# prototype.net
KiCad netlist of a schematic drawn in EAGLE
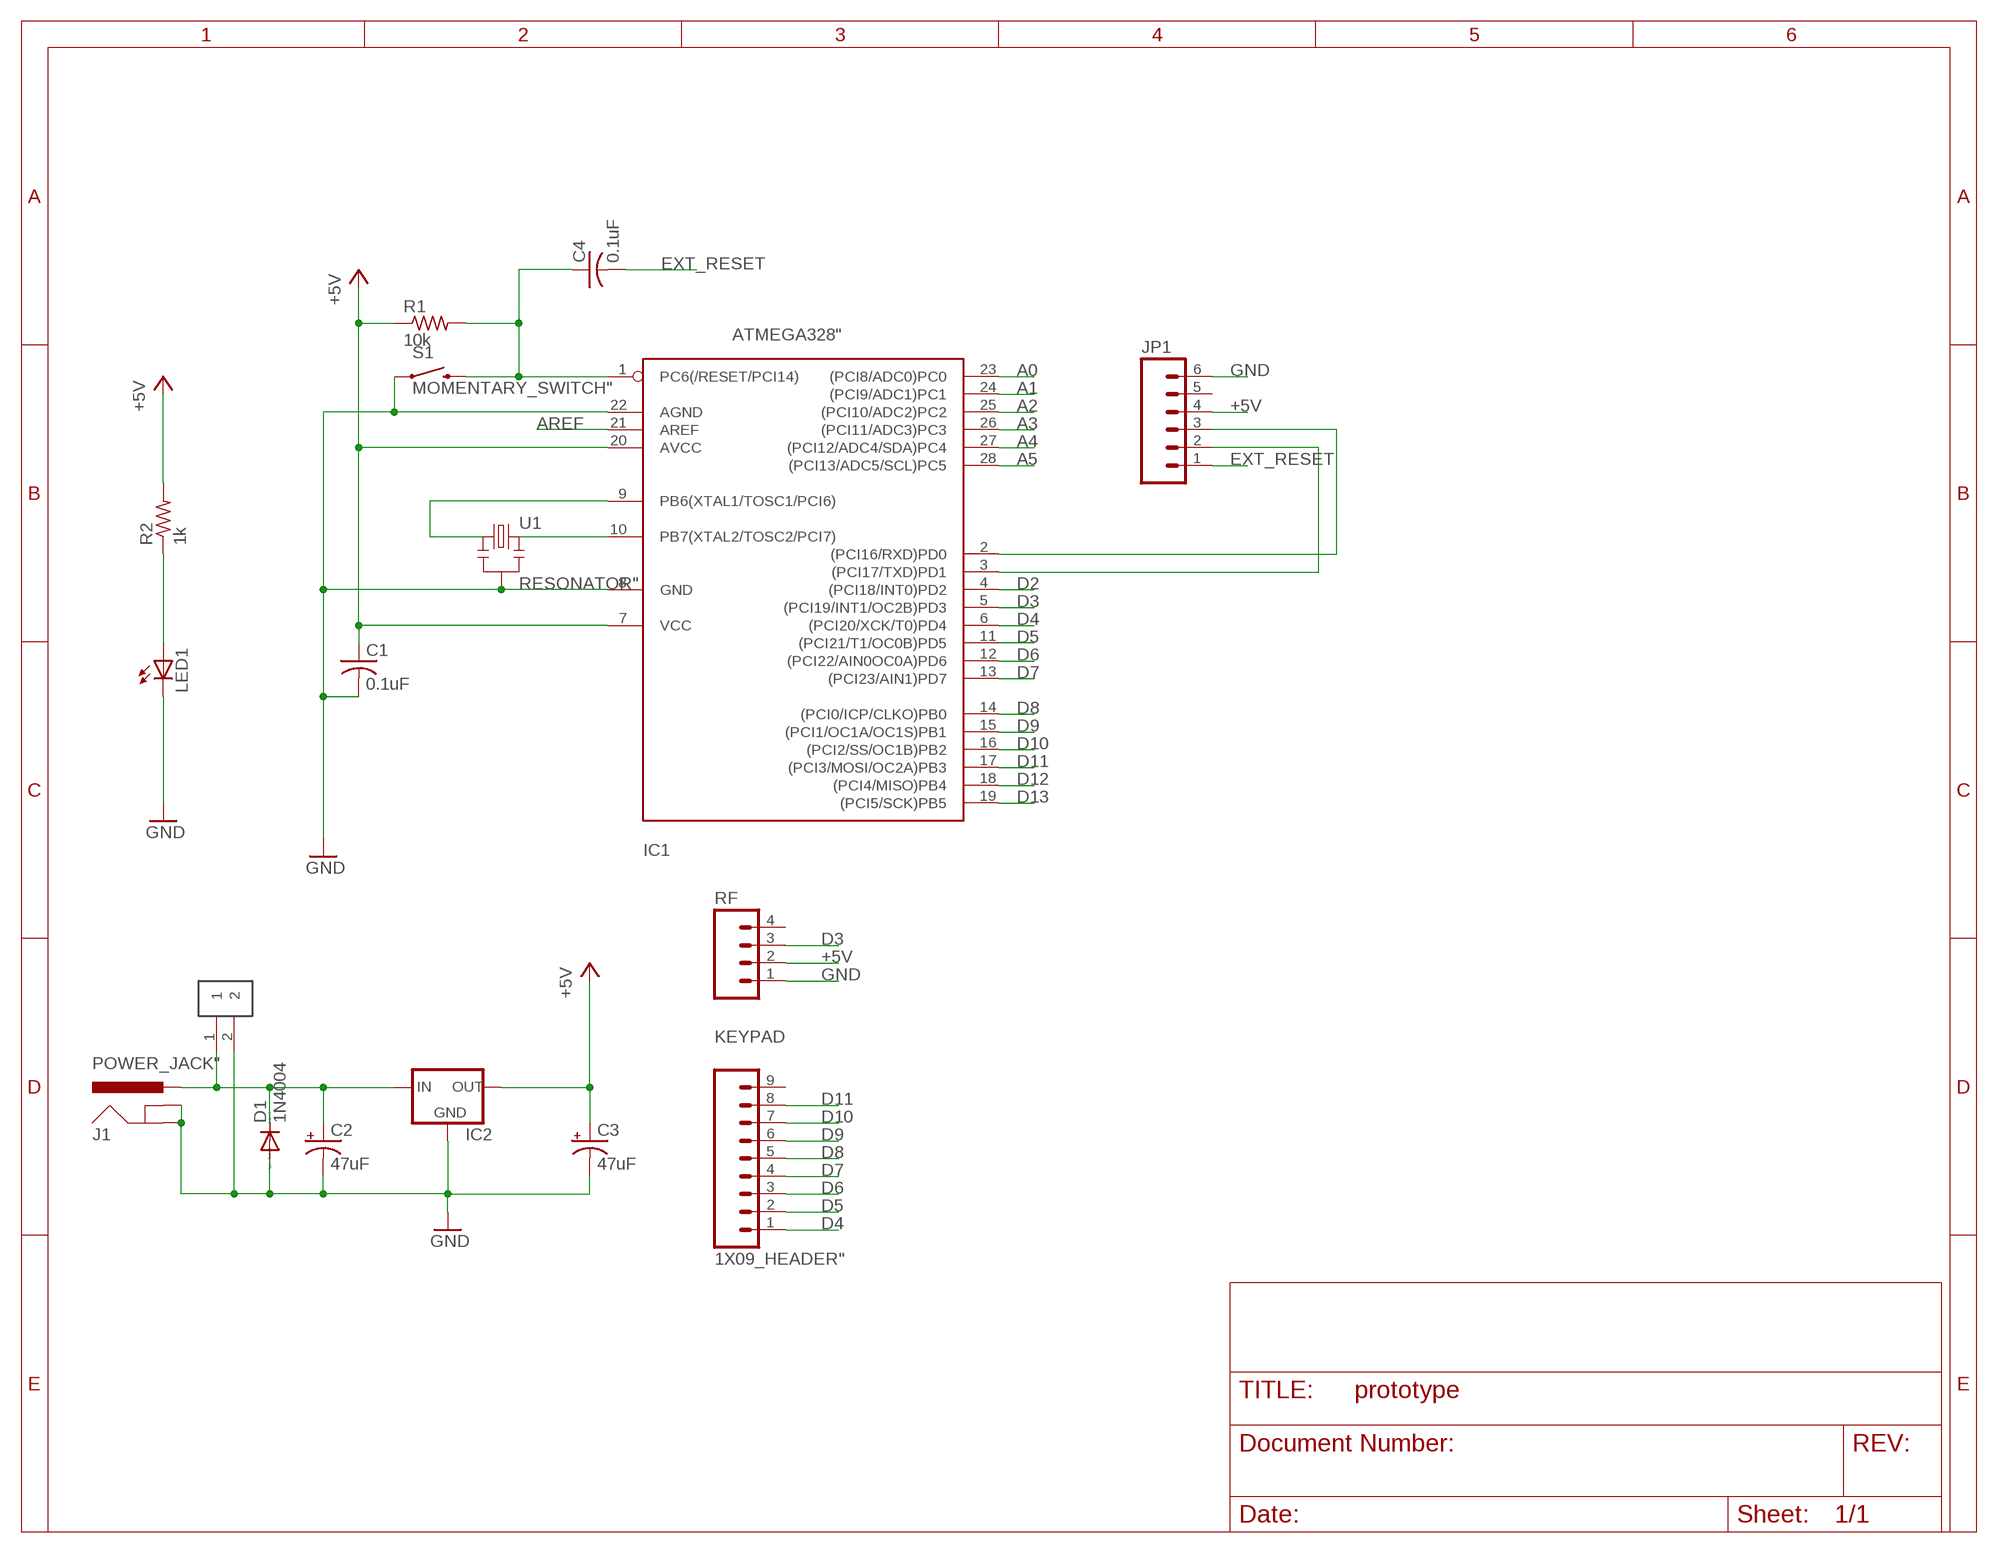
[diagram p0: schematic, sheet 1]

(export (version "E")
  (design (tool "Eeschema 10.0.6"))
  (components
    (comp (ref "C1")
      (value "0.1uF")
      (footprint "eagle-import:UNPOLARIZED_CAP")
      (libsource (lib "eagle-import") (part "UNPOLARIZED_CAP{dblquote}"))
    )
    (comp (ref "C2")
      (value "47uF")
      (footprint "eagle-import:ELECTROLYTIC_CAP")
      (libsource (lib "eagle-import") (part "ELECTROLYTIC_CAP2.54MM"))
    )
    (comp (ref "C3")
      (value "47uF")
      (footprint "eagle-import:ELECTROLYTIC_CAP")
      (libsource (lib "eagle-import") (part "ELECTROLYTIC_CAP2.54MM"))
    )
    (comp (ref "C4")
      (value "0.1uF")
      (footprint "eagle-import:UNPOLARIZED_CAP")
      (libsource (lib "eagle-import") (part "UNPOLARIZED_CAP{dblquote}"))
    )
    (comp (ref "D1")
      (value "1N4004")
      (footprint "eagle-import:DO41-10")
      (libsource (lib "eagle-import") (part "1N4004"))
    )
    (comp (ref "IC1")
      (value "ATMEGA328\"")
      (footprint "eagle-import:ATMEGA328")
      (libsource (lib "eagle-import") (part "ATMEGA328{dblquote}"))
    )
    (comp (ref "IC2")
      (value "REGULATOR")
      (footprint "eagle-import:L4931_REGULATOR")
      (libsource (lib "eagle-import") (part "REGULATOR"))
    )
    (comp (ref "J1")
      (value "POWER_JACK\"")
      (footprint "eagle-import:POWER_JACK")
      (libsource (lib "eagle-import") (part "POWER_JACK{dblquote}"))
    )
    (comp (ref "JP1")
      (value "1X06_HEADER\"")
      (footprint "eagle-import:1X06_HEADER")
      (libsource (lib "eagle-import") (part "1X06_HEADER{dblquote}"))
    )
    (comp (ref "KEYPAD")
      (value "1X09_HEADER\"")
      (footprint "eagle-import:1X09_HEADER")
      (libsource (lib "eagle-import") (part "1X09_HEADER{dblquote}"))
    )
    (comp (ref "LED1")
      (value "LED3MM")
      (footprint "eagle-import:LED")
      (libsource (lib "eagle-import") (part "LED3MM"))
    )
    (comp (ref "R1")
      (value "10k")
      (footprint "eagle-import:RESISTOR")
      (libsource (lib "eagle-import") (part "RESISTOR1/6WATT"))
    )
    (comp (ref "R2")
      (value "1k")
      (footprint "eagle-import:RESISTOR")
      (libsource (lib "eagle-import") (part "RESISTOR1/6WATT"))
    )
    (comp (ref "RF")
      (value "1X04_HEADER\"")
      (footprint "eagle-import:1X04_HEADER")
      (libsource (lib "eagle-import") (part "1X04_HEADER{dblquote}"))
    )
    (comp (ref "S1")
      (value "MOMENTARY_SWITCH\"")
      (footprint "eagle-import:MOMENTARY_SWITCH")
      (libsource (lib "eagle-import") (part "MOMENTARY_SWITCH{dblquote}"))
    )
    (comp (ref "U$1")
      (value "1X02_HEADER")
      (footprint "eagle-import:1X02_HEADER")
      (libsource (lib "eagle-import") (part "1X02_HEADER"))
    )
    (comp (ref "U1")
      (value "RESONATOR\"")
      (footprint "eagle-import:RESONATOR")
      (libsource (lib "eagle-import") (part "RESONATOR{dblquote}"))
    )
  )
  (nets
    (net (code "1") (name "+5V") (class "Default")
      (node (ref "C1") (pin "1") (pinfunction "1_1") (pintype "passive"))
      (node (ref "C3") (pin "+") (pinfunction "+_+") (pintype "passive"))
      (node (ref "IC1") (pin "20") (pinfunction "AVCC_20") (pintype "bidirectional"))
      (node (ref "IC1") (pin "7") (pinfunction "VCC_7") (pintype "bidirectional"))
      (node (ref "IC2") (pin "OUT") (pinfunction "OUT_OUT") (pintype "passive"))
      (node (ref "JP1") (pin "4") (pinfunction "4_4") (pintype "passive"))
      (node (ref "R1") (pin "1") (pinfunction "1_1") (pintype "passive"))
      (node (ref "R2") (pin "2") (pinfunction "2_2") (pintype "passive"))
      (node (ref "RF") (pin "2") (pinfunction "2_2") (pintype "passive"))
    )
    (net (code "2") (name "/A0") (class "Default")
      (node (ref "IC1") (pin "23") (pinfunction "(PCI8/ADC0)PC0_23") (pintype "bidirectional"))
    )
    (net (code "3") (name "/A1") (class "Default")
      (node (ref "IC1") (pin "24") (pinfunction "(PCI9/ADC1)PC1_24") (pintype "bidirectional"))
    )
    (net (code "4") (name "/A2") (class "Default")
      (node (ref "IC1") (pin "25") (pinfunction "(PCI10/ADC2)PC2_25") (pintype "bidirectional"))
    )
    (net (code "5") (name "/A3") (class "Default")
      (node (ref "IC1") (pin "26") (pinfunction "(PCI11/ADC3)PC3_26") (pintype "bidirectional"))
    )
    (net (code "6") (name "/A4") (class "Default")
      (node (ref "IC1") (pin "27") (pinfunction "(PCI12/ADC4/SDA)PC4_27") (pintype "bidirectional"))
    )
    (net (code "7") (name "/A5") (class "Default")
      (node (ref "IC1") (pin "28") (pinfunction "(PCI13/ADC5/SCL)PC5_28") (pintype "bidirectional"))
    )
    (net (code "8") (name "/AREF") (class "Default")
      (node (ref "IC1") (pin "21") (pinfunction "AREF_21") (pintype "bidirectional"))
    )
    (net (code "9") (name "/D2") (class "Default")
      (node (ref "IC1") (pin "4") (pinfunction "(PCI18/INT0)PD2_4") (pintype "bidirectional"))
    )
    (net (code "10") (name "/D3") (class "Default")
      (node (ref "IC1") (pin "5") (pinfunction "(PCI19/INT1/OC2B)PD3_5") (pintype "bidirectional"))
      (node (ref "RF") (pin "3") (pinfunction "3_3") (pintype "passive"))
    )
    (net (code "11") (name "/D4") (class "Default")
      (node (ref "IC1") (pin "6") (pinfunction "(PCI20/XCK/T0)PD4_6") (pintype "bidirectional"))
      (node (ref "KEYPAD") (pin "1") (pinfunction "1_1") (pintype "passive"))
    )
    (net (code "12") (name "/D5") (class "Default")
      (node (ref "IC1") (pin "11") (pinfunction "(PCI21/T1/OC0B)PD5_11") (pintype "bidirectional"))
      (node (ref "KEYPAD") (pin "2") (pinfunction "2_2") (pintype "passive"))
    )
    (net (code "13") (name "/D6") (class "Default")
      (node (ref "IC1") (pin "12") (pinfunction "(PCI22/AIN0OC0A)PD6_12") (pintype "bidirectional"))
      (node (ref "KEYPAD") (pin "3") (pinfunction "3_3") (pintype "passive"))
    )
    (net (code "14") (name "/D7") (class "Default")
      (node (ref "IC1") (pin "13") (pinfunction "(PCI23/AIN1)PD7_13") (pintype "bidirectional"))
      (node (ref "KEYPAD") (pin "4") (pinfunction "4_4") (pintype "passive"))
    )
    (net (code "15") (name "/D8") (class "Default")
      (node (ref "IC1") (pin "14") (pinfunction "(PCI0/ICP/CLKO)PB0_14") (pintype "bidirectional"))
      (node (ref "KEYPAD") (pin "5") (pinfunction "5_5") (pintype "passive"))
    )
    (net (code "16") (name "/D9") (class "Default")
      (node (ref "IC1") (pin "15") (pinfunction "(PCI1/OC1A/OC1S)PB1_15") (pintype "bidirectional"))
      (node (ref "KEYPAD") (pin "6") (pinfunction "6_6") (pintype "passive"))
    )
    (net (code "17") (name "/D10") (class "Default")
      (node (ref "IC1") (pin "16") (pinfunction "(PCI2/SS/OC1B)PB2_16") (pintype "bidirectional"))
      (node (ref "KEYPAD") (pin "7") (pinfunction "7_7") (pintype "passive"))
    )
    (net (code "18") (name "/D11") (class "Default")
      (node (ref "IC1") (pin "17") (pinfunction "(PCI3/MOSI/OC2A)PB3_17") (pintype "bidirectional"))
      (node (ref "KEYPAD") (pin "8") (pinfunction "8_8") (pintype "passive"))
    )
    (net (code "19") (name "/D12") (class "Default")
      (node (ref "IC1") (pin "18") (pinfunction "(PCI4/MISO)PB4_18") (pintype "bidirectional"))
    )
    (net (code "20") (name "/D13") (class "Default")
      (node (ref "IC1") (pin "19") (pinfunction "(PCI5/SCK)PB5_19") (pintype "bidirectional"))
    )
    (net (code "21") (name "/EXT_RESET") (class "Default")
      (node (ref "C4") (pin "2") (pinfunction "2_2") (pintype "passive"))
      (node (ref "JP1") (pin "1") (pinfunction "1_1") (pintype "passive"))
    )
    (net (code "22") (name "GND") (class "Default")
      (node (ref "C1") (pin "2") (pinfunction "2_2") (pintype "passive"))
      (node (ref "C2") (pin "-") (pinfunction "-_-") (pintype "passive"))
      (node (ref "C3") (pin "-") (pinfunction "-_-") (pintype "passive"))
      (node (ref "D1") (pin "A") (pinfunction "A_A") (pintype "passive"))
      (node (ref "IC1") (pin "22") (pinfunction "AGND_22") (pintype "bidirectional"))
      (node (ref "IC1") (pin "8") (pinfunction "GND_8") (pintype "bidirectional"))
      (node (ref "IC2") (pin "GND") (pinfunction "GND_GND") (pintype "input"))
      (node (ref "J1") (pin "GND") (pinfunction "GND_GND") (pintype "bidirectional"))
      (node (ref "J1") (pin "GNDBREAK") (pinfunction "GNDBREAK_GNDBREAK") (pintype "bidirectional"))
      (node (ref "JP1") (pin "6") (pinfunction "6_6") (pintype "passive"))
      (node (ref "LED1") (pin "K") (pinfunction "C_K") (pintype "passive"))
      (node (ref "RF") (pin "1") (pinfunction "1_1") (pintype "passive"))
      (node (ref "S1") (pin "1") (pinfunction "1_1") (pintype "passive"))
      (node (ref "U$1") (pin "2") (pinfunction "2_2") (pintype "bidirectional"))
      (node (ref "U1") (pin "2") (pinfunction "2_2") (pintype "passive"))
    )
    (net (code "23") (name "Net-(C2-Pad+)") (class "Default")
      (node (ref "C2") (pin "+") (pinfunction "+_+") (pintype "passive"))
      (node (ref "D1") (pin "C") (pinfunction "C_C") (pintype "passive"))
      (node (ref "IC2") (pin "IN") (pinfunction "IN_IN") (pintype "input"))
      (node (ref "J1") (pin "PWR") (pinfunction "PWR_PWR") (pintype "bidirectional"))
      (node (ref "U$1") (pin "1") (pinfunction "1_1") (pintype "bidirectional"))
    )
    (net (code "24") (name "Net-(IC1-(PCI16{slash}RXD)PD0)") (class "Default")
      (node (ref "IC1") (pin "2") (pinfunction "(PCI16/RXD)PD0_2") (pintype "bidirectional"))
      (node (ref "JP1") (pin "3") (pinfunction "3_3") (pintype "passive"))
    )
    (net (code "25") (name "Net-(IC1-(PCI17{slash}TXD)PD1)") (class "Default")
      (node (ref "IC1") (pin "3") (pinfunction "(PCI17/TXD)PD1_3") (pintype "bidirectional"))
      (node (ref "JP1") (pin "2") (pinfunction "2_2") (pintype "passive"))
    )
    (net (code "26") (name "Net-(IC1-PB6(XTAL1{slash}TOSC1{slash}PCI6))") (class "Default")
      (node (ref "IC1") (pin "9") (pinfunction "PB6(XTAL1/TOSC1/PCI6)_9") (pintype "bidirectional"))
      (node (ref "U1") (pin "1") (pinfunction "1_1") (pintype "passive"))
    )
    (net (code "27") (name "Net-(IC1-PB7(XTAL2{slash}TOSC2{slash}PCI7))") (class "Default")
      (node (ref "IC1") (pin "10") (pinfunction "PB7(XTAL2/TOSC2/PCI7)_10") (pintype "bidirectional"))
      (node (ref "U1") (pin "3") (pinfunction "3_3") (pintype "passive"))
    )
    (net (code "28") (name "Net-(IC1-PC6({slash}RESET{slash}PCI14))") (class "Default")
      (node (ref "C4") (pin "1") (pinfunction "1_1") (pintype "passive"))
      (node (ref "IC1") (pin "1") (pinfunction "PC6(/RESET/PCI14)_1") (pintype "bidirectional"))
      (node (ref "R1") (pin "2") (pinfunction "2_2") (pintype "passive"))
      (node (ref "S1") (pin "3") (pinfunction "2_3") (pintype "passive"))
    )
    (net (code "29") (name "Net-(LED1-PadA)") (class "Default")
      (node (ref "LED1") (pin "A") (pinfunction "A_A") (pintype "passive"))
      (node (ref "R2") (pin "1") (pinfunction "1_1") (pintype "passive"))
    )
    (net (code "30") (name "unconnected-(JP1-Pad5)") (class "Default")
      (node (ref "JP1") (pin "5") (pinfunction "5_5") (pintype "passive"))
    )
    (net (code "31") (name "unconnected-(KEYPAD-Pad9)") (class "Default")
      (node (ref "KEYPAD") (pin "9") (pinfunction "9_9") (pintype "passive"))
    )
    (net (code "32") (name "unconnected-(RF-Pad4)") (class "Default")
      (node (ref "RF") (pin "4") (pinfunction "4_4") (pintype "passive"))
    )
  )
)
